# diskohedron4w_reve.net
KiCad netlist of a schematic drawn in EAGLE
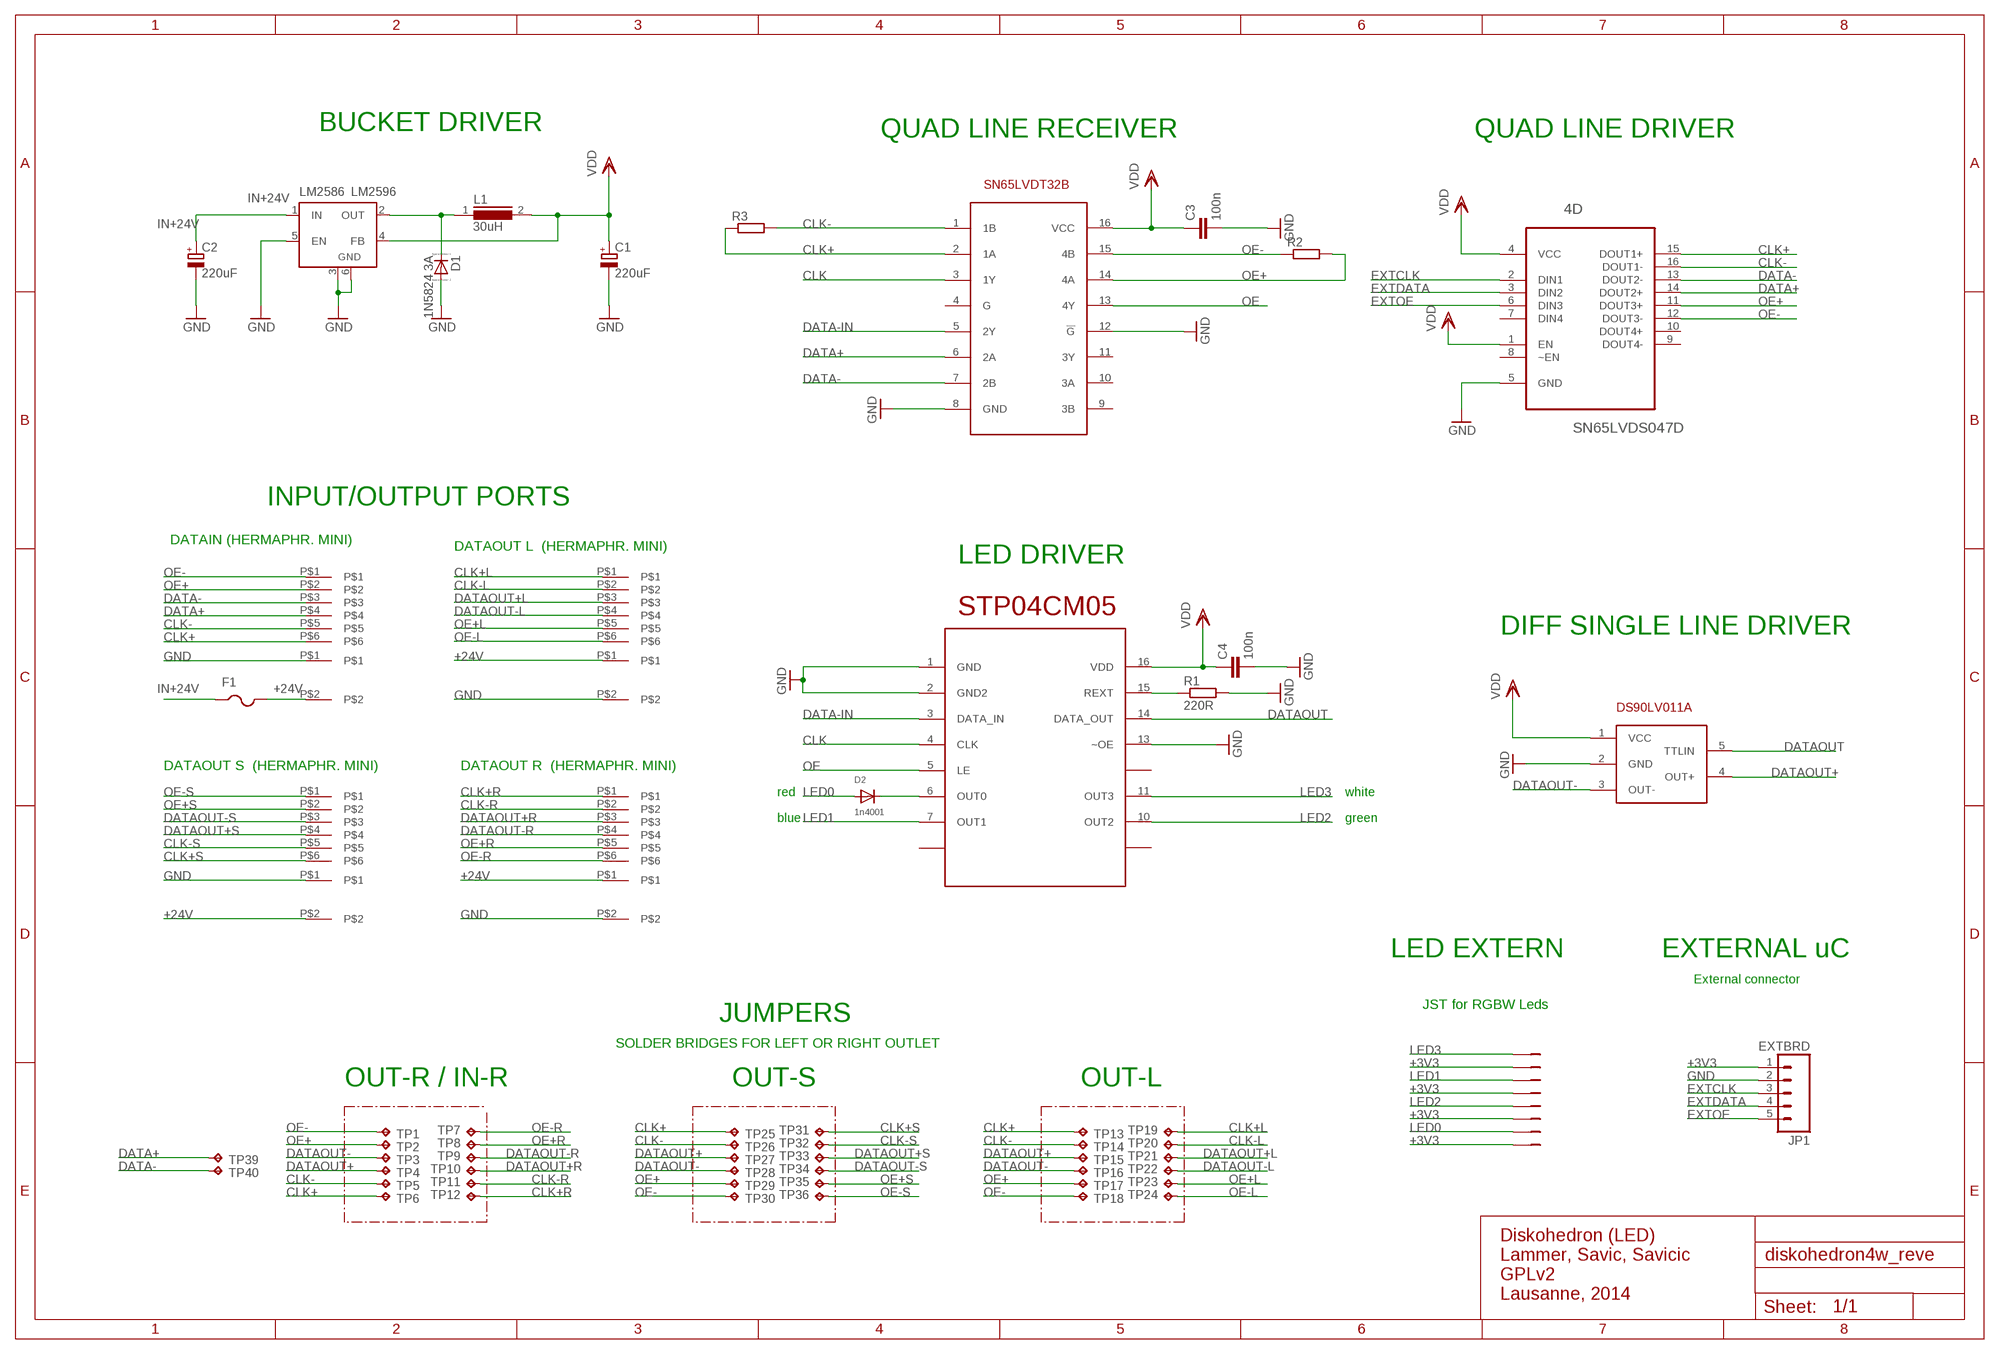
[diagram p0: schematic, sheet 1]

(export (version "E")
  (design (tool "Eeschema 10.0.6"))
  (components
    (comp (ref "1D")
      (value "DS90LV011A")
      (footprint "eagle-import:SOT23-5")
      (libsource (lib "eagle-import") (part "DS90LV011A"))
    )
    (comp (ref "4D")
      (value "SN65LVDS047D")
      (footprint "eagle-import:SOIC127P600X175-16N")
      (libsource (lib "eagle-import") (part "SN65LVDS047D"))
    )
    (comp (ref "4R")
      (value "SN65LVDST32")
      (footprint "eagle-import:SOIC16")
      (libsource (lib "eagle-import") (part "SN65LVDST32"))
    )
    (comp (ref "C1")
      (value "220uF")
      (footprint "eagle-import:153CLV-1010")
      (libsource (lib "eagle-import") (part "CPOL-EU153CLV-1010"))
    )
    (comp (ref "C2")
      (value "220uF")
      (footprint "eagle-import:153CLV-1010")
      (libsource (lib "eagle-import") (part "CPOL-EU153CLV-1010"))
    )
    (comp (ref "C3")
      (value "100n")
      (footprint "eagle-import:C0805")
      (libsource (lib "eagle-import") (part "C-EUC0805"))
    )
    (comp (ref "C4")
      (value "100n")
      (footprint "eagle-import:C0805")
      (libsource (lib "eagle-import") (part "C-EUC0805"))
    )
    (comp (ref "D1")
      (value "1N5824 3A")
      (footprint "eagle-import:DIODE_SMC")
      (libsource (lib "eagle-import") (part "DIODE_E-SMC"))
    )
    (comp (ref "D2")
      (value "1n4001")
      (footprint "eagle-import:SMADIODE")
      (libsource (lib "eagle-import") (part "DIODESMA"))
    )
    (comp (ref "F1")
      (value "PTCFUSE-1812")
      (footprint "eagle-import:1812")
      (libsource (lib "eagle-import") (part "PTCFUSE-1812"))
    )
    (comp (ref "IN1")
      (value "HERMAPHRODITMINI6PIN")
      (footprint "eagle-import:HERMAPHRODITMINI6PIN")
      (libsource (lib "eagle-import") (part "HERMAPHRODITMINI6PIN"))
    )
    (comp (ref "JP1")
      (value "EXTBRD")
      (footprint "eagle-import:1X05")
      (libsource (lib "eagle-import") (part "M05PTH"))
    )
    (comp (ref "JST")
      (value "8PIN-ZH")
      (footprint "eagle-import:B8B-ZH")
      (libsource (lib "eagle-import") (part "8PIN-ZH"))
    )
    (comp (ref "L1")
      (value "30uH")
      (footprint "eagle-import:DR127")
      (libsource (lib "eagle-import") (part "DR127"))
    )
    (comp (ref "LM2586")
      (value "LM2596")
      (footprint "eagle-import:TO263-5")
      (libsource (lib "eagle-import") (part "LM2596S"))
    )
    (comp (ref "OUT-L")
      (value "HERMAPHRODITMINI6PIN")
      (footprint "eagle-import:HERMAPHRODITMINI6PIN")
      (libsource (lib "eagle-import") (part "HERMAPHRODITMINI6PIN"))
    )
    (comp (ref "OUT-R")
      (value "HERMAPHRODITMINI6PIN")
      (footprint "eagle-import:HERMAPHRODITMINI6PIN")
      (libsource (lib "eagle-import") (part "HERMAPHRODITMINI6PIN"))
    )
    (comp (ref "OUT-S")
      (value "HERMAPHRODITMINI6PIN")
      (footprint "eagle-import:HERMAPHRODITMINI6PIN")
      (libsource (lib "eagle-import") (part "HERMAPHRODITMINI6PIN"))
    )
    (comp (ref "POWERIN")
      (value "HERMAPHRODIT2PIN")
      (footprint "eagle-import:HERMAPHRODIT2PIN")
      (libsource (lib "eagle-import") (part "HERMAPHRODIT2PIN"))
    )
    (comp (ref "POWEROUT-L")
      (value "HERMAPHRODIT2PIN")
      (footprint "eagle-import:HERMAPHRODIT2PIN")
      (libsource (lib "eagle-import") (part "HERMAPHRODIT2PIN"))
    )
    (comp (ref "POWEROUT-R")
      (value "HERMAPHRODIT2PIN")
      (footprint "eagle-import:HERMAPHRODIT2PIN")
      (libsource (lib "eagle-import") (part "HERMAPHRODIT2PIN"))
    )
    (comp (ref "POWEROUT-S")
      (value "HERMAPHRODIT2PIN")
      (footprint "eagle-import:HERMAPHRODIT2PIN")
      (libsource (lib "eagle-import") (part "HERMAPHRODIT2PIN"))
    )
    (comp (ref "R1")
      (value "220R")
      (footprint "eagle-import:M0805")
      (libsource (lib "eagle-import") (part "resistor_R-EU_M0805"))
    )
    (comp (ref "R2")
      (value "R-EU_R0603")
      (footprint "eagle-import:R0603")
      (libsource (lib "eagle-import") (part "R-EU_R0603"))
    )
    (comp (ref "R3")
      (value "R-EU_R0603")
      (footprint "eagle-import:R0603")
      (libsource (lib "eagle-import") (part "R-EU_R0603"))
    )
    (comp (ref "STP04")
      (value "STP04CM05")
      (footprint "eagle-import:TSSOP16")
      (libsource (lib "eagle-import") (part "STP04CM05"))
    )
    (comp (ref "TP1")
      (value "TPTP12SQ")
      (footprint "eagle-import:TP12SQ")
      (libsource (lib "eagle-import") (part "TPTP12SQ"))
    )
    (comp (ref "TP2")
      (value "TPTP12SQ")
      (footprint "eagle-import:TP12SQ")
      (libsource (lib "eagle-import") (part "TPTP12SQ"))
    )
    (comp (ref "TP3")
      (value "TPTP09SQ")
      (footprint "eagle-import:TP09SQ")
      (libsource (lib "eagle-import") (part "TPTP09SQ"))
    )
    (comp (ref "TP4")
      (value "TPTP09SQ")
      (footprint "eagle-import:TP09SQ")
      (libsource (lib "eagle-import") (part "TPTP09SQ"))
    )
    (comp (ref "TP5")
      (value "TPTP12SQ")
      (footprint "eagle-import:TP12SQ")
      (libsource (lib "eagle-import") (part "TPTP12SQ"))
    )
    (comp (ref "TP6")
      (value "TPTP12SQ")
      (footprint "eagle-import:TP12SQ")
      (libsource (lib "eagle-import") (part "TPTP12SQ"))
    )
    (comp (ref "TP7")
      (value "TPTP12SQ")
      (footprint "eagle-import:TP12SQ")
      (libsource (lib "eagle-import") (part "TPTP12SQ"))
    )
    (comp (ref "TP8")
      (value "TPTP12SQ")
      (footprint "eagle-import:TP12SQ")
      (libsource (lib "eagle-import") (part "TPTP12SQ"))
    )
    (comp (ref "TP9")
      (value "TPTP20SQ")
      (footprint "eagle-import:TP20SQ")
      (libsource (lib "eagle-import") (part "TPTP20SQ"))
    )
    (comp (ref "TP10")
      (value "TPTP20SQ")
      (footprint "eagle-import:TP20SQ")
      (libsource (lib "eagle-import") (part "TPTP20SQ"))
    )
    (comp (ref "TP11")
      (value "TPTP12SQ")
      (footprint "eagle-import:TP12SQ")
      (libsource (lib "eagle-import") (part "TPTP12SQ"))
    )
    (comp (ref "TP12")
      (value "TPTP12SQ")
      (footprint "eagle-import:TP12SQ")
      (libsource (lib "eagle-import") (part "TPTP12SQ"))
    )
    (comp (ref "TP13")
      (value "TPTP12SQ")
      (footprint "eagle-import:TP12SQ")
      (libsource (lib "eagle-import") (part "TPTP12SQ"))
    )
    (comp (ref "TP14")
      (value "TPTP12SQ")
      (footprint "eagle-import:TP12SQ")
      (libsource (lib "eagle-import") (part "TPTP12SQ"))
    )
    (comp (ref "TP15")
      (value "TPTP12SQ")
      (footprint "eagle-import:TP12SQ")
      (libsource (lib "eagle-import") (part "TPTP12SQ"))
    )
    (comp (ref "TP16")
      (value "TPTP12SQ")
      (footprint "eagle-import:TP12SQ")
      (libsource (lib "eagle-import") (part "TPTP12SQ"))
    )
    (comp (ref "TP17")
      (value "TPTP12SQ")
      (footprint "eagle-import:TP12SQ")
      (libsource (lib "eagle-import") (part "TPTP12SQ"))
    )
    (comp (ref "TP18")
      (value "TPTP12SQ")
      (footprint "eagle-import:TP12SQ")
      (libsource (lib "eagle-import") (part "TPTP12SQ"))
    )
    (comp (ref "TP19")
      (value "TPTP12SQ")
      (footprint "eagle-import:TP12SQ")
      (libsource (lib "eagle-import") (part "TPTP12SQ"))
    )
    (comp (ref "TP20")
      (value "TPTP12SQ")
      (footprint "eagle-import:TP12SQ")
      (libsource (lib "eagle-import") (part "TPTP12SQ"))
    )
    (comp (ref "TP21")
      (value "TPTP12SQ")
      (footprint "eagle-import:TP12SQ")
      (libsource (lib "eagle-import") (part "TPTP12SQ"))
    )
    (comp (ref "TP22")
      (value "TPTP12SQ")
      (footprint "eagle-import:TP12SQ")
      (libsource (lib "eagle-import") (part "TPTP12SQ"))
    )
    (comp (ref "TP23")
      (value "TPTP12SQ")
      (footprint "eagle-import:TP12SQ")
      (libsource (lib "eagle-import") (part "TPTP12SQ"))
    )
    (comp (ref "TP24")
      (value "TPTP12SQ")
      (footprint "eagle-import:TP12SQ")
      (libsource (lib "eagle-import") (part "TPTP12SQ"))
    )
    (comp (ref "TP25")
      (value "TPTP12SQ")
      (footprint "eagle-import:TP12SQ")
      (libsource (lib "eagle-import") (part "TPTP12SQ"))
    )
    (comp (ref "TP26")
      (value "TPTP12SQ")
      (footprint "eagle-import:TP12SQ")
      (libsource (lib "eagle-import") (part "TPTP12SQ"))
    )
    (comp (ref "TP27")
      (value "TPTP12SQ")
      (footprint "eagle-import:TP12SQ")
      (libsource (lib "eagle-import") (part "TPTP12SQ"))
    )
    (comp (ref "TP28")
      (value "TPTP12SQ")
      (footprint "eagle-import:TP12SQ")
      (libsource (lib "eagle-import") (part "TPTP12SQ"))
    )
    (comp (ref "TP29")
      (value "TPTP12SQ")
      (footprint "eagle-import:TP12SQ")
      (libsource (lib "eagle-import") (part "TPTP12SQ"))
    )
    (comp (ref "TP30")
      (value "TPTP12SQ")
      (footprint "eagle-import:TP12SQ")
      (libsource (lib "eagle-import") (part "TPTP12SQ"))
    )
    (comp (ref "TP31")
      (value "TPTP12SQ")
      (footprint "eagle-import:TP12SQ")
      (libsource (lib "eagle-import") (part "TPTP12SQ"))
    )
    (comp (ref "TP32")
      (value "TPTP12SQ")
      (footprint "eagle-import:TP12SQ")
      (libsource (lib "eagle-import") (part "TPTP12SQ"))
    )
    (comp (ref "TP33")
      (value "TPTP12SQ")
      (footprint "eagle-import:TP12SQ")
      (libsource (lib "eagle-import") (part "TPTP12SQ"))
    )
    (comp (ref "TP34")
      (value "TPTP12SQ")
      (footprint "eagle-import:TP12SQ")
      (libsource (lib "eagle-import") (part "TPTP12SQ"))
    )
    (comp (ref "TP35")
      (value "TPTP12SQ")
      (footprint "eagle-import:TP12SQ")
      (libsource (lib "eagle-import") (part "TPTP12SQ"))
    )
    (comp (ref "TP36")
      (value "TPTP12SQ")
      (footprint "eagle-import:TP12SQ")
      (libsource (lib "eagle-import") (part "TPTP12SQ"))
    )
    (comp (ref "TP39")
      (value "TPTP09SQ")
      (footprint "eagle-import:TP09SQ")
      (libsource (lib "eagle-import") (part "TPTP09SQ"))
    )
    (comp (ref "TP40")
      (value "TPTP09SQ")
      (footprint "eagle-import:TP09SQ")
      (libsource (lib "eagle-import") (part "TPTP09SQ"))
    )
  )
  (nets
    (net (code "1") (name "/+24V") (class "Default")
      (node (ref "F1") (pin "2") (pinfunction "2_2") (pintype "passive"))
      (node (ref "POWERIN") (pin "P$2") (pinfunction "P$2_P$2") (pintype "bidirectional"))
      (node (ref "POWEROUT-L") (pin "P$1") (pinfunction "P$1_P$1") (pintype "bidirectional"))
      (node (ref "POWEROUT-R") (pin "P$1") (pinfunction "P$1_P$1") (pintype "bidirectional"))
      (node (ref "POWEROUT-S") (pin "P$2") (pinfunction "P$2_P$2") (pintype "bidirectional"))
    )
    (net (code "2") (name "/CLK") (class "Default")
      (node (ref "4R") (pin "3") (pinfunction "1Y_3") (pintype "bidirectional"))
      (node (ref "STP04") (pin "4") (pinfunction "CLK_4") (pintype "bidirectional"))
    )
    (net (code "3") (name "/CLK+") (class "Default")
      (node (ref "4D") (pin "15") (pinfunction "DOUT1+_15") (pintype "output"))
      (node (ref "4R") (pin "2") (pinfunction "1A_2") (pintype "bidirectional"))
      (node (ref "IN1") (pin "P$6") (pinfunction "P$6_P$6") (pintype "bidirectional"))
      (node (ref "R3") (pin "1") (pinfunction "1_1") (pintype "passive"))
      (node (ref "TP13") (pin "TP") (pinfunction "TP_TP") (pintype "input"))
      (node (ref "TP25") (pin "TP") (pinfunction "TP_TP") (pintype "input"))
      (node (ref "TP6") (pin "TP") (pinfunction "TP_TP") (pintype "input"))
    )
    (net (code "4") (name "/CLK+L") (class "Default")
      (node (ref "OUT-L") (pin "P$1") (pinfunction "P$1_P$1") (pintype "bidirectional"))
      (node (ref "TP19") (pin "TP") (pinfunction "TP_TP") (pintype "input"))
    )
    (net (code "5") (name "/CLK+R") (class "Default")
      (node (ref "OUT-R") (pin "P$1") (pinfunction "P$1_P$1") (pintype "bidirectional"))
      (node (ref "TP12") (pin "TP") (pinfunction "TP_TP") (pintype "input"))
    )
    (net (code "6") (name "/CLK+S") (class "Default")
      (node (ref "OUT-S") (pin "P$6") (pinfunction "P$6_P$6") (pintype "bidirectional"))
      (node (ref "TP31") (pin "TP") (pinfunction "TP_TP") (pintype "input"))
    )
    (net (code "7") (name "/CLK-") (class "Default")
      (node (ref "4D") (pin "16") (pinfunction "DOUT1-_16") (pintype "output"))
      (node (ref "4R") (pin "1") (pinfunction "1B_1") (pintype "bidirectional"))
      (node (ref "IN1") (pin "P$5") (pinfunction "P$5_P$5") (pintype "bidirectional"))
      (node (ref "R3") (pin "2") (pinfunction "2_2") (pintype "passive"))
      (node (ref "TP14") (pin "TP") (pinfunction "TP_TP") (pintype "input"))
      (node (ref "TP26") (pin "TP") (pinfunction "TP_TP") (pintype "input"))
      (node (ref "TP5") (pin "TP") (pinfunction "TP_TP") (pintype "input"))
    )
    (net (code "8") (name "/CLK-L") (class "Default")
      (node (ref "OUT-L") (pin "P$2") (pinfunction "P$2_P$2") (pintype "bidirectional"))
      (node (ref "TP20") (pin "TP") (pinfunction "TP_TP") (pintype "input"))
    )
    (net (code "9") (name "/CLK-R") (class "Default")
      (node (ref "OUT-R") (pin "P$2") (pinfunction "P$2_P$2") (pintype "bidirectional"))
      (node (ref "TP11") (pin "TP") (pinfunction "TP_TP") (pintype "input"))
    )
    (net (code "10") (name "/CLK-S") (class "Default")
      (node (ref "OUT-S") (pin "P$5") (pinfunction "P$5_P$5") (pintype "bidirectional"))
      (node (ref "TP32") (pin "TP") (pinfunction "TP_TP") (pintype "input"))
    )
    (net (code "11") (name "/DATA+") (class "Default")
      (node (ref "4D") (pin "14") (pinfunction "DOUT2+_14") (pintype "output"))
      (node (ref "4R") (pin "6") (pinfunction "2A_6") (pintype "bidirectional"))
      (node (ref "IN1") (pin "P$4") (pinfunction "P$4_P$4") (pintype "bidirectional"))
      (node (ref "TP39") (pin "TP") (pinfunction "TP_TP") (pintype "input"))
    )
    (net (code "12") (name "/DATA-") (class "Default")
      (node (ref "4D") (pin "13") (pinfunction "DOUT2-_13") (pintype "output"))
      (node (ref "4R") (pin "7") (pinfunction "2B_7") (pintype "bidirectional"))
      (node (ref "IN1") (pin "P$3") (pinfunction "P$3_P$3") (pintype "bidirectional"))
      (node (ref "TP40") (pin "TP") (pinfunction "TP_TP") (pintype "input"))
    )
    (net (code "13") (name "/DATA-IN") (class "Default")
      (node (ref "4R") (pin "5") (pinfunction "2Y_5") (pintype "bidirectional"))
      (node (ref "STP04") (pin "3") (pinfunction "DATA_IN_3") (pintype "bidirectional"))
    )
    (net (code "14") (name "/DATAOUT") (class "Default")
      (node (ref "1D") (pin "5") (pinfunction "TTLIN_5") (pintype "bidirectional"))
      (node (ref "STP04") (pin "14") (pinfunction "DATA_OUT_14") (pintype "bidirectional"))
    )
    (net (code "15") (name "/DATAOUT+") (class "Default")
      (node (ref "1D") (pin "4") (pinfunction "OUT+_4") (pintype "bidirectional"))
      (node (ref "TP15") (pin "TP") (pinfunction "TP_TP") (pintype "input"))
      (node (ref "TP27") (pin "TP") (pinfunction "TP_TP") (pintype "input"))
      (node (ref "TP4") (pin "TP") (pinfunction "TP_TP") (pintype "input"))
    )
    (net (code "16") (name "/DATAOUT+L") (class "Default")
      (node (ref "OUT-L") (pin "P$3") (pinfunction "P$3_P$3") (pintype "bidirectional"))
      (node (ref "TP21") (pin "TP") (pinfunction "TP_TP") (pintype "input"))
    )
    (net (code "17") (name "/DATAOUT+R") (class "Default")
      (node (ref "OUT-R") (pin "P$3") (pinfunction "P$3_P$3") (pintype "bidirectional"))
      (node (ref "TP10") (pin "TP") (pinfunction "TP_TP") (pintype "input"))
    )
    (net (code "18") (name "/DATAOUT+S") (class "Default")
      (node (ref "OUT-S") (pin "P$4") (pinfunction "P$4_P$4") (pintype "bidirectional"))
      (node (ref "TP33") (pin "TP") (pinfunction "TP_TP") (pintype "input"))
    )
    (net (code "19") (name "/DATAOUT-") (class "Default")
      (node (ref "1D") (pin "3") (pinfunction "OUT-_3") (pintype "bidirectional"))
      (node (ref "TP16") (pin "TP") (pinfunction "TP_TP") (pintype "input"))
      (node (ref "TP28") (pin "TP") (pinfunction "TP_TP") (pintype "input"))
      (node (ref "TP3") (pin "TP") (pinfunction "TP_TP") (pintype "input"))
    )
    (net (code "20") (name "/DATAOUT-L") (class "Default")
      (node (ref "OUT-L") (pin "P$4") (pinfunction "P$4_P$4") (pintype "bidirectional"))
      (node (ref "TP22") (pin "TP") (pinfunction "TP_TP") (pintype "input"))
    )
    (net (code "21") (name "/DATAOUT-R") (class "Default")
      (node (ref "OUT-R") (pin "P$4") (pinfunction "P$4_P$4") (pintype "bidirectional"))
      (node (ref "TP9") (pin "TP") (pinfunction "TP_TP") (pintype "input"))
    )
    (net (code "22") (name "/DATAOUT-S") (class "Default")
      (node (ref "OUT-S") (pin "P$3") (pinfunction "P$3_P$3") (pintype "bidirectional"))
      (node (ref "TP34") (pin "TP") (pinfunction "TP_TP") (pintype "input"))
    )
    (net (code "23") (name "/EXTCLK") (class "Default")
      (node (ref "4D") (pin "2") (pinfunction "DIN1_2") (pintype "input"))
      (node (ref "JP1") (pin "3") (pinfunction "3_3") (pintype "passive"))
    )
    (net (code "24") (name "/EXTDATA") (class "Default")
      (node (ref "4D") (pin "3") (pinfunction "DIN2_3") (pintype "input"))
      (node (ref "JP1") (pin "4") (pinfunction "4_4") (pintype "passive"))
    )
    (net (code "25") (name "/EXTOE") (class "Default")
      (node (ref "4D") (pin "6") (pinfunction "DIN3_6") (pintype "input"))
      (node (ref "JP1") (pin "5") (pinfunction "5_5") (pintype "passive"))
    )
    (net (code "26") (name "/IN+24V") (class "Default")
      (node (ref "C2") (pin "+") (pinfunction "+_+") (pintype "passive"))
      (node (ref "F1") (pin "1") (pinfunction "1_1") (pintype "passive"))
      (node (ref "LM2586") (pin "1") (pinfunction "IN_1") (pintype "input"))
    )
    (net (code "27") (name "/LED0") (class "Default")
      (node (ref "D2") (pin "A") (pinfunction "A_A") (pintype "passive"))
      (node (ref "JST") (pin "7") (pinfunction "1_7") (pintype "passive"))
    )
    (net (code "28") (name "/LED1") (class "Default")
      (node (ref "JST") (pin "3") (pinfunction "1_3") (pintype "passive"))
      (node (ref "STP04") (pin "7") (pinfunction "OUT1_7") (pintype "bidirectional"))
    )
    (net (code "29") (name "/LED2") (class "Default")
      (node (ref "JST") (pin "5") (pinfunction "1_5") (pintype "passive"))
      (node (ref "STP04") (pin "10") (pinfunction "OUT2_10") (pintype "bidirectional"))
    )
    (net (code "30") (name "/LED3") (class "Default")
      (node (ref "JST") (pin "1") (pinfunction "1_1") (pintype "passive"))
      (node (ref "STP04") (pin "11") (pinfunction "OUT3_11") (pintype "bidirectional"))
    )
    (net (code "31") (name "/OE") (class "Default")
      (node (ref "4R") (pin "13") (pinfunction "4Y_13") (pintype "bidirectional"))
      (node (ref "STP04") (pin "5") (pinfunction "LE_5") (pintype "bidirectional"))
    )
    (net (code "32") (name "/OE+") (class "Default")
      (node (ref "4D") (pin "11") (pinfunction "DOUT3+_11") (pintype "output"))
      (node (ref "4R") (pin "14") (pinfunction "4A_14") (pintype "bidirectional"))
      (node (ref "IN1") (pin "P$2") (pinfunction "P$2_P$2") (pintype "bidirectional"))
      (node (ref "R2") (pin "2") (pinfunction "2_2") (pintype "passive"))
      (node (ref "TP17") (pin "TP") (pinfunction "TP_TP") (pintype "input"))
      (node (ref "TP2") (pin "TP") (pinfunction "TP_TP") (pintype "input"))
      (node (ref "TP29") (pin "TP") (pinfunction "TP_TP") (pintype "input"))
    )
    (net (code "33") (name "/OE+L") (class "Default")
      (node (ref "OUT-L") (pin "P$5") (pinfunction "P$5_P$5") (pintype "bidirectional"))
      (node (ref "TP23") (pin "TP") (pinfunction "TP_TP") (pintype "input"))
    )
    (net (code "34") (name "/OE+R") (class "Default")
      (node (ref "OUT-R") (pin "P$5") (pinfunction "P$5_P$5") (pintype "bidirectional"))
      (node (ref "TP8") (pin "TP") (pinfunction "TP_TP") (pintype "input"))
    )
    (net (code "35") (name "/OE+S") (class "Default")
      (node (ref "OUT-S") (pin "P$2") (pinfunction "P$2_P$2") (pintype "bidirectional"))
      (node (ref "TP35") (pin "TP") (pinfunction "TP_TP") (pintype "input"))
    )
    (net (code "36") (name "/OE-") (class "Default")
      (node (ref "4D") (pin "12") (pinfunction "DOUT3-_12") (pintype "output"))
      (node (ref "4R") (pin "15") (pinfunction "4B_15") (pintype "bidirectional"))
      (node (ref "IN1") (pin "P$1") (pinfunction "P$1_P$1") (pintype "bidirectional"))
      (node (ref "R2") (pin "1") (pinfunction "1_1") (pintype "passive"))
      (node (ref "TP1") (pin "TP") (pinfunction "TP_TP") (pintype "input"))
      (node (ref "TP18") (pin "TP") (pinfunction "TP_TP") (pintype "input"))
      (node (ref "TP30") (pin "TP") (pinfunction "TP_TP") (pintype "input"))
    )
    (net (code "37") (name "/OE-L") (class "Default")
      (node (ref "OUT-L") (pin "P$6") (pinfunction "P$6_P$6") (pintype "bidirectional"))
      (node (ref "TP24") (pin "TP") (pinfunction "TP_TP") (pintype "input"))
    )
    (net (code "38") (name "/OE-R") (class "Default")
      (node (ref "OUT-R") (pin "P$6") (pinfunction "P$6_P$6") (pintype "bidirectional"))
      (node (ref "TP7") (pin "TP") (pinfunction "TP_TP") (pintype "input"))
    )
    (net (code "39") (name "/OE-S") (class "Default")
      (node (ref "OUT-S") (pin "P$1") (pinfunction "P$1_P$1") (pintype "bidirectional"))
      (node (ref "TP36") (pin "TP") (pinfunction "TP_TP") (pintype "input"))
    )
    (net (code "40") (name "GND") (class "Default")
      (node (ref "1D") (pin "2") (pinfunction "GND_2") (pintype "bidirectional"))
      (node (ref "4D") (pin "5") (pinfunction "GND_5") (pintype "passive"))
      (node (ref "4R") (pin "12") (pinfunction "~{G}_12") (pintype "bidirectional"))
      (node (ref "4R") (pin "8") (pinfunction "GND_8") (pintype "bidirectional"))
      (node (ref "C1") (pin "-") (pinfunction "-_-") (pintype "passive"))
      (node (ref "C2") (pin "-") (pinfunction "-_-") (pintype "passive"))
      (node (ref "C3") (pin "2") (pinfunction "2_2") (pintype "passive"))
      (node (ref "C4") (pin "2") (pinfunction "2_2") (pintype "passive"))
      (node (ref "D1") (pin "A") (pinfunction "C_A") (pintype "passive"))
      (node (ref "JP1") (pin "2") (pinfunction "2_2") (pintype "passive"))
      (node (ref "LM2586") (pin "3") (pinfunction "GND_3") (pintype "power_in"))
      (node (ref "LM2586") (pin "5") (pinfunction "EN_5") (pintype "input"))
      (node (ref "LM2586") (pin "6") (pinfunction "GND_6") (pintype "power_in"))
      (node (ref "POWERIN") (pin "P$1") (pinfunction "P$1_P$1") (pintype "bidirectional"))
      (node (ref "POWEROUT-L") (pin "P$2") (pinfunction "P$2_P$2") (pintype "bidirectional"))
      (node (ref "POWEROUT-R") (pin "P$2") (pinfunction "P$2_P$2") (pintype "bidirectional"))
      (node (ref "POWEROUT-S") (pin "P$1") (pinfunction "P$1_P$1") (pintype "bidirectional"))
      (node (ref "R1") (pin "2") (pinfunction "2_2") (pintype "passive"))
      (node (ref "STP04") (pin "1") (pinfunction "GND_1") (pintype "bidirectional"))
      (node (ref "STP04") (pin "13") (pinfunction "~{OE}_13") (pintype "bidirectional"))
      (node (ref "STP04") (pin "2") (pinfunction "GND2_2") (pintype "bidirectional"))
    )
    (net (code "41") (name "Net-(D1-A)") (class "Default")
      (node (ref "D1") (pin "C") (pinfunction "A_C") (pintype "passive"))
      (node (ref "L1") (pin "1") (pinfunction "1_1") (pintype "passive"))
      (node (ref "LM2586") (pin "2") (pinfunction "OUT_2") (pintype "output"))
    )
    (net (code "42") (name "Net-(STP04-OUT0)") (class "Default")
      (node (ref "D2") (pin "C") (pinfunction "C_C") (pintype "passive"))
      (node (ref "STP04") (pin "6") (pinfunction "OUT0_6") (pintype "bidirectional"))
    )
    (net (code "43") (name "Net-(STP04-REXT)") (class "Default")
      (node (ref "R1") (pin "1") (pinfunction "1_1") (pintype "passive"))
      (node (ref "STP04") (pin "15") (pinfunction "REXT_15") (pintype "bidirectional"))
    )
    (net (code "44") (name "VDD") (class "Default")
      (node (ref "1D") (pin "1") (pinfunction "VCC_1") (pintype "bidirectional"))
      (node (ref "4D") (pin "1") (pinfunction "EN_1") (pintype "input"))
      (node (ref "4D") (pin "4") (pinfunction "VCC_4") (pintype "power_in"))
      (node (ref "4R") (pin "16") (pinfunction "VCC_16") (pintype "bidirectional"))
      (node (ref "C1") (pin "+") (pinfunction "+_+") (pintype "passive"))
      (node (ref "C3") (pin "1") (pinfunction "1_1") (pintype "passive"))
      (node (ref "C4") (pin "1") (pinfunction "1_1") (pintype "passive"))
      (node (ref "JP1") (pin "1") (pinfunction "1_1") (pintype "passive"))
      (node (ref "JST") (pin "2") (pinfunction "1_2") (pintype "passive"))
      (node (ref "JST") (pin "4") (pinfunction "1_4") (pintype "passive"))
      (node (ref "JST") (pin "6") (pinfunction "1_6") (pintype "passive"))
      (node (ref "JST") (pin "8") (pinfunction "1_8") (pintype "passive"))
      (node (ref "L1") (pin "2") (pinfunction "2_2") (pintype "passive"))
      (node (ref "LM2586") (pin "4") (pinfunction "FB_4") (pintype "input"))
      (node (ref "STP04") (pin "16") (pinfunction "VDD_16") (pintype "bidirectional"))
    )
    (net (code "45") (name "unconnected-(4D-DIN4-Pad7)") (class "Default")
      (node (ref "4D") (pin "7") (pinfunction "DIN4_7") (pintype "input"))
    )
    (net (code "46") (name "unconnected-(4D-DOUT4+-Pad10)") (class "Default")
      (node (ref "4D") (pin "10") (pinfunction "DOUT4+_10") (pintype "output"))
    )
    (net (code "47") (name "unconnected-(4D-DOUT4--Pad9)") (class "Default")
      (node (ref "4D") (pin "9") (pinfunction "DOUT4-_9") (pintype "output"))
    )
    (net (code "48") (name "unconnected-(4D-~{EN}-Pad8)") (class "Default")
      (node (ref "4D") (pin "8") (pinfunction "~{EN}_8") (pintype "input"))
    )
    (net (code "49") (name "unconnected-(4R-3A-Pad10)") (class "Default")
      (node (ref "4R") (pin "10") (pinfunction "3A_10") (pintype "bidirectional"))
    )
    (net (code "50") (name "unconnected-(4R-3B-Pad9)") (class "Default")
      (node (ref "4R") (pin "9") (pinfunction "3B_9") (pintype "bidirectional"))
    )
    (net (code "51") (name "unconnected-(4R-3Y-Pad11)") (class "Default")
      (node (ref "4R") (pin "11") (pinfunction "3Y_11") (pintype "bidirectional"))
    )
    (net (code "52") (name "unconnected-(4R-G-Pad4)") (class "Default")
      (node (ref "4R") (pin "4") (pinfunction "G_4") (pintype "bidirectional"))
    )
    (net (code "53") (name "unconnected-(STP04-N.C1-Pad8)") (class "Default")
      (node (ref "STP04") (pin "8") (pinfunction "N.C1_8") (pintype "bidirectional"))
    )
    (net (code "54") (name "unconnected-(STP04-NC-Pad9)") (class "Default")
      (node (ref "STP04") (pin "9") (pinfunction "NC_9") (pintype "bidirectional"))
    )
    (net (code "55") (name "unconnected-(STP04-NC3-Pad12)") (class "Default")
      (node (ref "STP04") (pin "12") (pinfunction "NC3_12") (pintype "bidirectional"))
    )
  )
)
